# bluepod.net
KiCad netlist of a schematic drawn in EAGLE
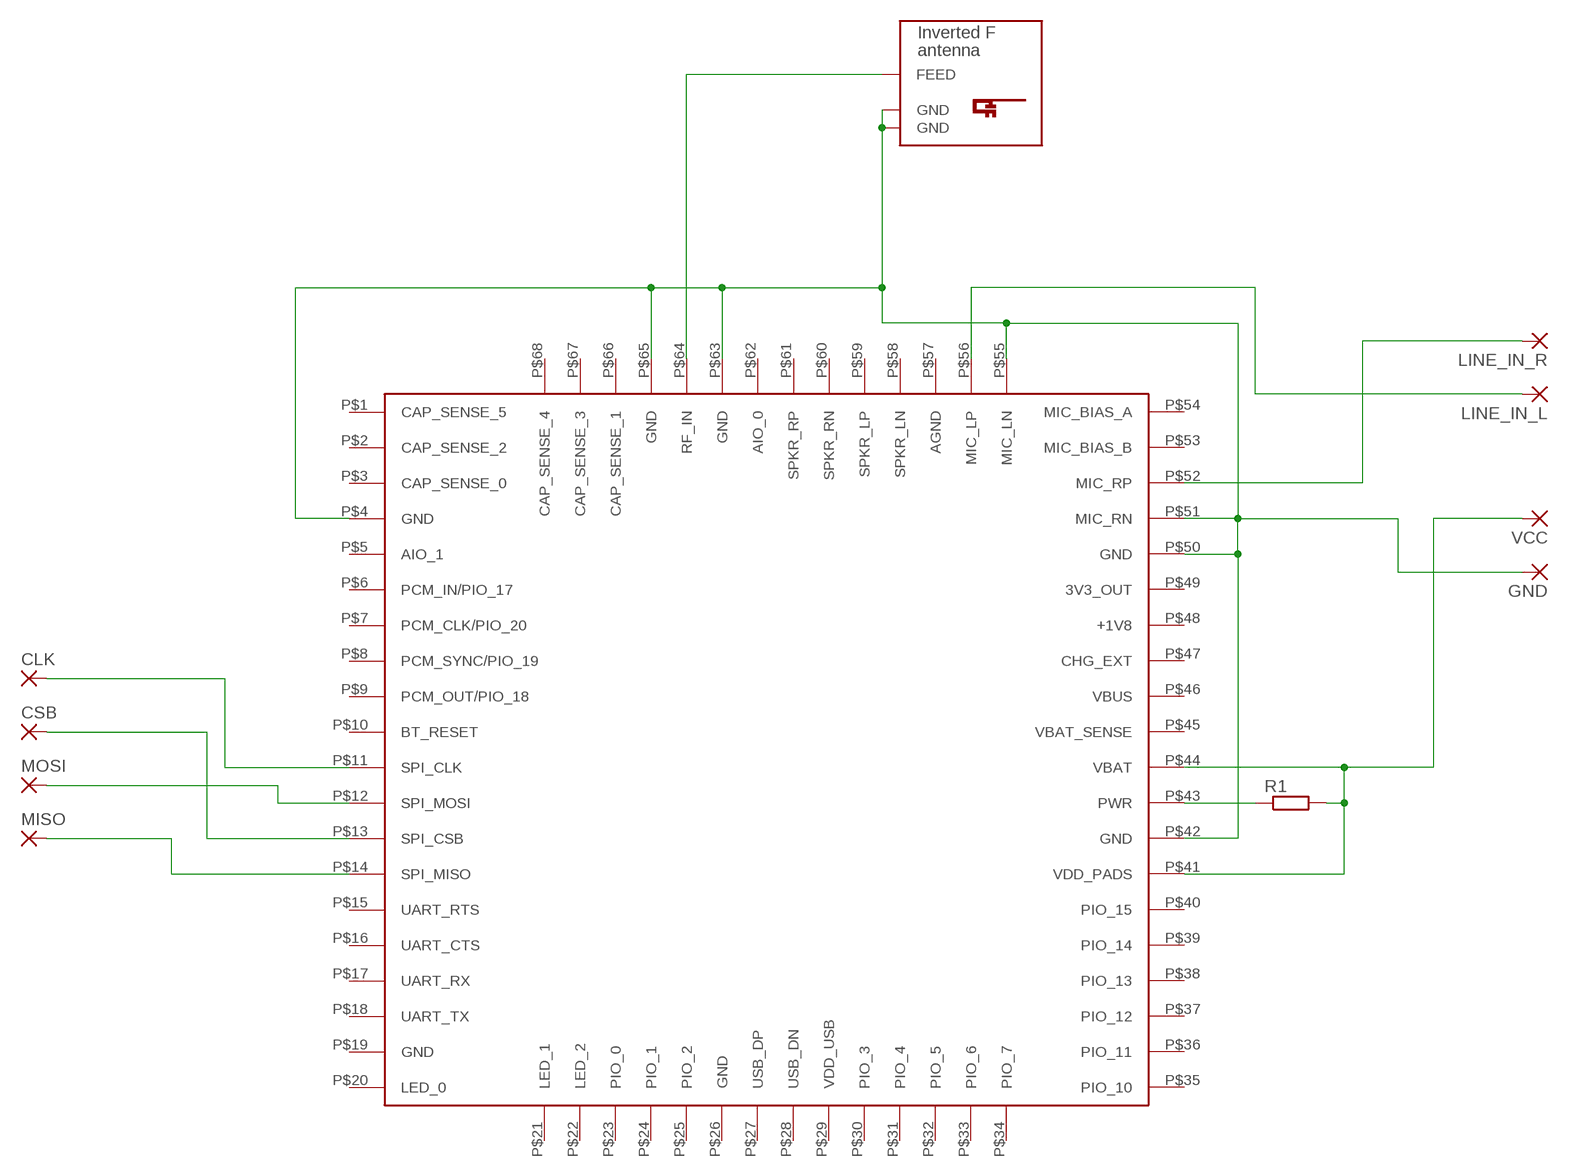
[diagram p0: schematic, sheet 1]

(export (version "E")
  (design (tool "Eeschema 10.0.6"))
  (components
    (comp (ref "CLK")
      (value "2,54/1,0")
      (footprint "eagle-import:2,54_1,0")
      (libsource (lib "eagle-import") (part "2,54/1,0"))
    )
    (comp (ref "CSB")
      (value "2,54/1,0")
      (footprint "eagle-import:2,54_1,0")
      (libsource (lib "eagle-import") (part "2,54/1,0"))
    )
    (comp (ref "GND")
      (value "2,54/1,0")
      (footprint "eagle-import:2,54_1,0")
      (libsource (lib "eagle-import") (part "2,54/1,0"))
    )
    (comp (ref "LINE_IN_L")
      (value "2,54/1,0")
      (footprint "eagle-import:2,54_1,0")
      (libsource (lib "eagle-import") (part "2,54/1,0"))
    )
    (comp (ref "LINE_IN_R")
      (value "2,54/1,0")
      (footprint "eagle-import:2,54_1,0")
      (libsource (lib "eagle-import") (part "2,54/1,0"))
    )
    (comp (ref "MISO")
      (value "2,54/1,0")
      (footprint "eagle-import:2,54_1,0")
      (libsource (lib "eagle-import") (part "2,54/1,0"))
    )
    (comp (ref "MOSI")
      (value "2,54/1,0")
      (footprint "eagle-import:2,54_1,0")
      (libsource (lib "eagle-import") (part "2,54/1,0"))
    )
    (comp (ref "R1")
      (value "R-EU_0207/5V")
      (footprint "eagle-import:0207_5V")
      (libsource (lib "eagle-import") (part "R-EU_0207/5V"))
    )
    (comp (ref "U$1")
      (value "BTM875-B")
      (footprint "eagle-import:STANDARD")
      (libsource (lib "eagle-import") (part "BTM875-B"))
    )
    (comp (ref "U$2")
      (value "INVERTED_F_ANTENNA+0")
      (footprint "eagle-import:DN007+0")
      (libsource (lib "eagle-import") (part "INVERTED_F_ANTENNA+0"))
    )
    (comp (ref "VCC")
      (value "2,54/1,0")
      (footprint "eagle-import:2,54_1,0")
      (libsource (lib "eagle-import") (part "2,54/1,0"))
    )
  )
  (nets
    (net (code "1") (name "Net-(CLK-P)") (class "Default")
      (node (ref "CLK") (pin "1") (pinfunction "P_1") (pintype "passive"))
      (node (ref "U$1") (pin "P$11") (pinfunction "SPI_CLK_P$11") (pintype "bidirectional"))
    )
    (net (code "2") (name "Net-(CSB-P)") (class "Default")
      (node (ref "CSB") (pin "1") (pinfunction "P_1") (pintype "passive"))
      (node (ref "U$1") (pin "P$13") (pinfunction "SPI_CSB_P$13") (pintype "bidirectional"))
    )
    (net (code "3") (name "Net-(GND-P)") (class "Default")
      (node (ref "GND") (pin "1") (pinfunction "P_1") (pintype "passive"))
      (node (ref "U$1") (pin "P$4") (pinfunction "GND_P$4") (pintype "bidirectional"))
      (node (ref "U$1") (pin "P$42") (pinfunction "GND_P$42") (pintype "bidirectional"))
      (node (ref "U$1") (pin "P$50") (pinfunction "GND_P$50") (pintype "bidirectional"))
      (node (ref "U$1") (pin "P$51") (pinfunction "MIC_RN_P$51") (pintype "bidirectional"))
      (node (ref "U$1") (pin "P$55") (pinfunction "MIC_LN_P$55") (pintype "bidirectional"))
      (node (ref "U$1") (pin "P$63") (pinfunction "GND_P$63") (pintype "bidirectional"))
      (node (ref "U$1") (pin "P$65") (pinfunction "GND_P$65") (pintype "bidirectional"))
      (node (ref "U$2") (pin "GND") (pinfunction "GND_GND") (pintype "bidirectional"))
      (node (ref "U$2") (pin "GND@1") (pinfunction "GND_GND@1") (pintype "bidirectional"))
    )
    (net (code "4") (name "Net-(LINE_IN_L-P)") (class "Default")
      (node (ref "LINE_IN_L") (pin "1") (pinfunction "P_1") (pintype "passive"))
      (node (ref "U$1") (pin "P$56") (pinfunction "MIC_LP_P$56") (pintype "bidirectional"))
    )
    (net (code "5") (name "Net-(LINE_IN_R-P)") (class "Default")
      (node (ref "LINE_IN_R") (pin "1") (pinfunction "P_1") (pintype "passive"))
      (node (ref "U$1") (pin "P$52") (pinfunction "MIC_RP_P$52") (pintype "bidirectional"))
    )
    (net (code "6") (name "Net-(MISO-P)") (class "Default")
      (node (ref "MISO") (pin "1") (pinfunction "P_1") (pintype "passive"))
      (node (ref "U$1") (pin "P$14") (pinfunction "SPI_MISO_P$14") (pintype "bidirectional"))
    )
    (net (code "7") (name "Net-(MOSI-P)") (class "Default")
      (node (ref "MOSI") (pin "1") (pinfunction "P_1") (pintype "passive"))
      (node (ref "U$1") (pin "P$12") (pinfunction "SPI_MOSI_P$12") (pintype "bidirectional"))
    )
    (net (code "8") (name "Net-(U$1-PWR)") (class "Default")
      (node (ref "R1") (pin "1") (pinfunction "1_1") (pintype "passive"))
      (node (ref "U$1") (pin "P$43") (pinfunction "PWR_P$43") (pintype "bidirectional"))
    )
    (net (code "9") (name "Net-(U$1-RF_IN)") (class "Default")
      (node (ref "U$1") (pin "P$64") (pinfunction "RF_IN_P$64") (pintype "bidirectional"))
      (node (ref "U$2") (pin "FEED") (pinfunction "FEED_FEED") (pintype "bidirectional"))
    )
    (net (code "10") (name "Net-(U$1-VBAT)") (class "Default")
      (node (ref "R1") (pin "2") (pinfunction "2_2") (pintype "passive"))
      (node (ref "U$1") (pin "P$41") (pinfunction "VDD_PADS_P$41") (pintype "bidirectional"))
      (node (ref "U$1") (pin "P$44") (pinfunction "VBAT_P$44") (pintype "bidirectional"))
      (node (ref "VCC") (pin "1") (pinfunction "P_1") (pintype "passive"))
    )
    (net (code "11") (name "unconnected-(U$1-+1V8-PadP$48)") (class "Default")
      (node (ref "U$1") (pin "P$48") (pinfunction "+1V8_P$48") (pintype "bidirectional"))
    )
    (net (code "12") (name "unconnected-(U$1-3V3_OUT-PadP$49)") (class "Default")
      (node (ref "U$1") (pin "P$49") (pinfunction "3V3_OUT_P$49") (pintype "bidirectional"))
    )
    (net (code "13") (name "unconnected-(U$1-AGND-PadP$57)") (class "Default")
      (node (ref "U$1") (pin "P$57") (pinfunction "AGND_P$57") (pintype "bidirectional"))
    )
    (net (code "14") (name "unconnected-(U$1-AIO_0-PadP$62)") (class "Default")
      (node (ref "U$1") (pin "P$62") (pinfunction "AIO_0_P$62") (pintype "bidirectional"))
    )
    (net (code "15") (name "unconnected-(U$1-AIO_1-PadP$5)") (class "Default")
      (node (ref "U$1") (pin "P$5") (pinfunction "AIO_1_P$5") (pintype "bidirectional"))
    )
    (net (code "16") (name "unconnected-(U$1-BT_RESET-PadP$10)") (class "Default")
      (node (ref "U$1") (pin "P$10") (pinfunction "BT_RESET_P$10") (pintype "bidirectional"))
    )
    (net (code "17") (name "unconnected-(U$1-CAP_SENSE_0-PadP$3)") (class "Default")
      (node (ref "U$1") (pin "P$3") (pinfunction "CAP_SENSE_0_P$3") (pintype "bidirectional"))
    )
    (net (code "18") (name "unconnected-(U$1-CAP_SENSE_1-PadP$66)") (class "Default")
      (node (ref "U$1") (pin "P$66") (pinfunction "CAP_SENSE_1_P$66") (pintype "bidirectional"))
    )
    (net (code "19") (name "unconnected-(U$1-CAP_SENSE_2-PadP$2)") (class "Default")
      (node (ref "U$1") (pin "P$2") (pinfunction "CAP_SENSE_2_P$2") (pintype "bidirectional"))
    )
    (net (code "20") (name "unconnected-(U$1-CAP_SENSE_3-PadP$67)") (class "Default")
      (node (ref "U$1") (pin "P$67") (pinfunction "CAP_SENSE_3_P$67") (pintype "bidirectional"))
    )
    (net (code "21") (name "unconnected-(U$1-CAP_SENSE_4-PadP$68)") (class "Default")
      (node (ref "U$1") (pin "P$68") (pinfunction "CAP_SENSE_4_P$68") (pintype "bidirectional"))
    )
    (net (code "22") (name "unconnected-(U$1-CAP_SENSE_5-PadP$1)") (class "Default")
      (node (ref "U$1") (pin "P$1") (pinfunction "CAP_SENSE_5_P$1") (pintype "bidirectional"))
    )
    (net (code "23") (name "unconnected-(U$1-CHG_EXT-PadP$47)") (class "Default")
      (node (ref "U$1") (pin "P$47") (pinfunction "CHG_EXT_P$47") (pintype "bidirectional"))
    )
    (net (code "24") (name "unconnected-(U$1-GND-PadP$19)") (class "Default")
      (node (ref "U$1") (pin "P$19") (pinfunction "GND_P$19") (pintype "bidirectional"))
    )
    (net (code "25") (name "unconnected-(U$1-GND-PadP$26)") (class "Default")
      (node (ref "U$1") (pin "P$26") (pinfunction "GND_P$26") (pintype "bidirectional"))
    )
    (net (code "26") (name "unconnected-(U$1-LED_0-PadP$20)") (class "Default")
      (node (ref "U$1") (pin "P$20") (pinfunction "LED_0_P$20") (pintype "bidirectional"))
    )
    (net (code "27") (name "unconnected-(U$1-LED_1-PadP$21)") (class "Default")
      (node (ref "U$1") (pin "P$21") (pinfunction "LED_1_P$21") (pintype "bidirectional"))
    )
    (net (code "28") (name "unconnected-(U$1-LED_2-PadP$22)") (class "Default")
      (node (ref "U$1") (pin "P$22") (pinfunction "LED_2_P$22") (pintype "bidirectional"))
    )
    (net (code "29") (name "unconnected-(U$1-MIC_BIAS_A-PadP$54)") (class "Default")
      (node (ref "U$1") (pin "P$54") (pinfunction "MIC_BIAS_A_P$54") (pintype "bidirectional"))
    )
    (net (code "30") (name "unconnected-(U$1-MIC_BIAS_B-PadP$53)") (class "Default")
      (node (ref "U$1") (pin "P$53") (pinfunction "MIC_BIAS_B_P$53") (pintype "bidirectional"))
    )
    (net (code "31") (name "unconnected-(U$1-PCM_CLK{slash}PIO_20-PadP$7)") (class "Default")
      (node (ref "U$1") (pin "P$7") (pinfunction "PCM_CLK/PIO_20_P$7") (pintype "bidirectional"))
    )
    (net (code "32") (name "unconnected-(U$1-PCM_IN{slash}PIO_17-PadP$6)") (class "Default")
      (node (ref "U$1") (pin "P$6") (pinfunction "PCM_IN/PIO_17_P$6") (pintype "bidirectional"))
    )
    (net (code "33") (name "unconnected-(U$1-PCM_OUT{slash}PIO_18-PadP$9)") (class "Default")
      (node (ref "U$1") (pin "P$9") (pinfunction "PCM_OUT/PIO_18_P$9") (pintype "bidirectional"))
    )
    (net (code "34") (name "unconnected-(U$1-PCM_SYNC{slash}PIO_19-PadP$8)") (class "Default")
      (node (ref "U$1") (pin "P$8") (pinfunction "PCM_SYNC/PIO_19_P$8") (pintype "bidirectional"))
    )
    (net (code "35") (name "unconnected-(U$1-PIO_0-PadP$23)") (class "Default")
      (node (ref "U$1") (pin "P$23") (pinfunction "PIO_0_P$23") (pintype "bidirectional"))
    )
    (net (code "36") (name "unconnected-(U$1-PIO_1-PadP$24)") (class "Default")
      (node (ref "U$1") (pin "P$24") (pinfunction "PIO_1_P$24") (pintype "bidirectional"))
    )
    (net (code "37") (name "unconnected-(U$1-PIO_2-PadP$25)") (class "Default")
      (node (ref "U$1") (pin "P$25") (pinfunction "PIO_2_P$25") (pintype "bidirectional"))
    )
    (net (code "38") (name "unconnected-(U$1-PIO_3-PadP$30)") (class "Default")
      (node (ref "U$1") (pin "P$30") (pinfunction "PIO_3_P$30") (pintype "bidirectional"))
    )
    (net (code "39") (name "unconnected-(U$1-PIO_4-PadP$31)") (class "Default")
      (node (ref "U$1") (pin "P$31") (pinfunction "PIO_4_P$31") (pintype "bidirectional"))
    )
    (net (code "40") (name "unconnected-(U$1-PIO_5-PadP$32)") (class "Default")
      (node (ref "U$1") (pin "P$32") (pinfunction "PIO_5_P$32") (pintype "bidirectional"))
    )
    (net (code "41") (name "unconnected-(U$1-PIO_6-PadP$33)") (class "Default")
      (node (ref "U$1") (pin "P$33") (pinfunction "PIO_6_P$33") (pintype "bidirectional"))
    )
    (net (code "42") (name "unconnected-(U$1-PIO_7-PadP$34)") (class "Default")
      (node (ref "U$1") (pin "P$34") (pinfunction "PIO_7_P$34") (pintype "bidirectional"))
    )
    (net (code "43") (name "unconnected-(U$1-PIO_10-PadP$35)") (class "Default")
      (node (ref "U$1") (pin "P$35") (pinfunction "PIO_10_P$35") (pintype "bidirectional"))
    )
    (net (code "44") (name "unconnected-(U$1-PIO_11-PadP$36)") (class "Default")
      (node (ref "U$1") (pin "P$36") (pinfunction "PIO_11_P$36") (pintype "bidirectional"))
    )
    (net (code "45") (name "unconnected-(U$1-PIO_12-PadP$37)") (class "Default")
      (node (ref "U$1") (pin "P$37") (pinfunction "PIO_12_P$37") (pintype "bidirectional"))
    )
    (net (code "46") (name "unconnected-(U$1-PIO_13-PadP$38)") (class "Default")
      (node (ref "U$1") (pin "P$38") (pinfunction "PIO_13_P$38") (pintype "bidirectional"))
    )
    (net (code "47") (name "unconnected-(U$1-PIO_14-PadP$39)") (class "Default")
      (node (ref "U$1") (pin "P$39") (pinfunction "PIO_14_P$39") (pintype "bidirectional"))
    )
    (net (code "48") (name "unconnected-(U$1-PIO_15-PadP$40)") (class "Default")
      (node (ref "U$1") (pin "P$40") (pinfunction "PIO_15_P$40") (pintype "bidirectional"))
    )
    (net (code "49") (name "unconnected-(U$1-SPKR_LN-PadP$58)") (class "Default")
      (node (ref "U$1") (pin "P$58") (pinfunction "SPKR_LN_P$58") (pintype "bidirectional"))
    )
    (net (code "50") (name "unconnected-(U$1-SPKR_LP-PadP$59)") (class "Default")
      (node (ref "U$1") (pin "P$59") (pinfunction "SPKR_LP_P$59") (pintype "bidirectional"))
    )
    (net (code "51") (name "unconnected-(U$1-SPKR_RN-PadP$60)") (class "Default")
      (node (ref "U$1") (pin "P$60") (pinfunction "SPKR_RN_P$60") (pintype "bidirectional"))
    )
    (net (code "52") (name "unconnected-(U$1-SPKR_RP-PadP$61)") (class "Default")
      (node (ref "U$1") (pin "P$61") (pinfunction "SPKR_RP_P$61") (pintype "bidirectional"))
    )
    (net (code "53") (name "unconnected-(U$1-UART_CTS-PadP$16)") (class "Default")
      (node (ref "U$1") (pin "P$16") (pinfunction "UART_CTS_P$16") (pintype "bidirectional"))
    )
    (net (code "54") (name "unconnected-(U$1-UART_RTS-PadP$15)") (class "Default")
      (node (ref "U$1") (pin "P$15") (pinfunction "UART_RTS_P$15") (pintype "bidirectional"))
    )
    (net (code "55") (name "unconnected-(U$1-UART_RX-PadP$17)") (class "Default")
      (node (ref "U$1") (pin "P$17") (pinfunction "UART_RX_P$17") (pintype "bidirectional"))
    )
    (net (code "56") (name "unconnected-(U$1-UART_TX-PadP$18)") (class "Default")
      (node (ref "U$1") (pin "P$18") (pinfunction "UART_TX_P$18") (pintype "bidirectional"))
    )
    (net (code "57") (name "unconnected-(U$1-USB_DN-PadP$28)") (class "Default")
      (node (ref "U$1") (pin "P$28") (pinfunction "USB_DN_P$28") (pintype "bidirectional"))
    )
    (net (code "58") (name "unconnected-(U$1-USB_DP-PadP$27)") (class "Default")
      (node (ref "U$1") (pin "P$27") (pinfunction "USB_DP_P$27") (pintype "bidirectional"))
    )
    (net (code "59") (name "unconnected-(U$1-VBAT_SENSE-PadP$45)") (class "Default")
      (node (ref "U$1") (pin "P$45") (pinfunction "VBAT_SENSE_P$45") (pintype "bidirectional"))
    )
    (net (code "60") (name "unconnected-(U$1-VBUS-PadP$46)") (class "Default")
      (node (ref "U$1") (pin "P$46") (pinfunction "VBUS_P$46") (pintype "bidirectional"))
    )
    (net (code "61") (name "unconnected-(U$1-VDD_USB-PadP$29)") (class "Default")
      (node (ref "U$1") (pin "P$29") (pinfunction "VDD_USB_P$29") (pintype "bidirectional"))
    )
  )
)
